# Piirikaavio-HSM213-001-SPC.net
KiCad netlist of a schematic drawn in Altium Designer
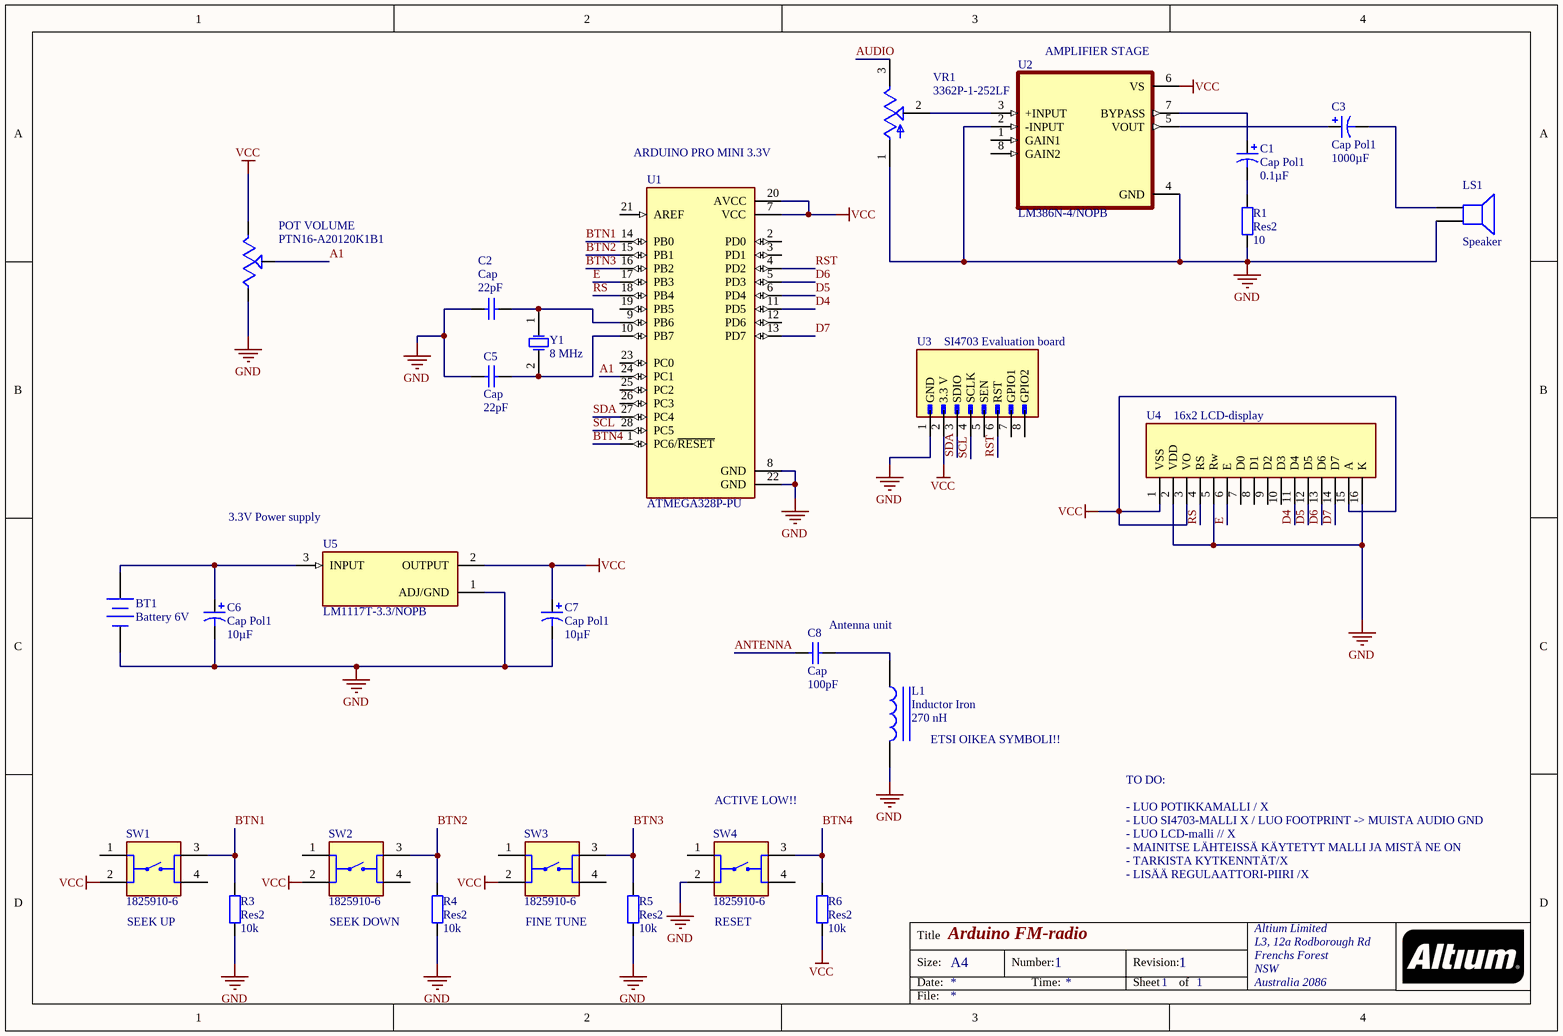
[diagram p0: Piirikaavio-HSM213-001-SPC.SchDoc]

(export (version "E")
  (design (tool "Eeschema 10.0.6"))
  (components
    (comp (ref "BT1")
      (value "Battery 6V")
      (footprint "BAT-2")
      (description "Multicell Battery")
      (fields (field (name "PUBLISHER") "Altium Limited"))
      (libsource (lib "Miscellaneous Devices") (part "Battery"))
    )
    (comp (ref "C1")
      (value "Cap Pol1")
      (footprint "RB7.6-15")
      (description "Polarized Capacitor (Radial)")
      (fields (field (name "ALTIUM_VALUE") "0.1µF") (field (name "PUBLISHER") "Altium Limited"))
      (libsource (lib "Miscellaneous Devices") (part "Cap Pol1"))
    )
    (comp (ref "C2")
      (value "Cap")
      (footprint "RAD-0.3")
      (description "Capacitor")
      (fields (field (name "ALTIUM_VALUE") "22pF") (field (name "PUBLISHER") "Altium Limited"))
      (libsource (lib "Miscellaneous Devices") (part "Cap"))
    )
    (comp (ref "C3")
      (value "Cap Pol1")
      (footprint "RB7.6-15")
      (description "Polarized Capacitor (Radial)")
      (fields (field (name "ALTIUM_VALUE") "1000µF") (field (name "PUBLISHER") "Altium Limited"))
      (libsource (lib "Miscellaneous Devices") (part "Cap Pol1"))
    )
    (comp (ref "C5")
      (value "Cap")
      (footprint "RAD-0.3")
      (description "Capacitor")
      (fields (field (name "ALTIUM_VALUE") "22pF") (field (name "PUBLISHER") "Altium Limited"))
      (libsource (lib "Miscellaneous Devices") (part "Cap"))
    )
    (comp (ref "C6")
      (value "Cap Pol1")
      (footprint "RB7.6-15")
      (description "Polarized Capacitor (Radial)")
      (fields (field (name "ALTIUM_VALUE") "10µF") (field (name "PUBLISHER") "Altium Limited"))
      (libsource (lib "Miscellaneous Devices") (part "Cap Pol1"))
    )
    (comp (ref "C7")
      (value "Cap Pol1")
      (footprint "RB7.6-15")
      (description "Polarized Capacitor (Radial)")
      (fields (field (name "ALTIUM_VALUE") "10µF") (field (name "PUBLISHER") "Altium Limited"))
      (libsource (lib "Miscellaneous Devices") (part "Cap Pol1"))
    )
    (comp (ref "C8")
      (value "Cap")
      (footprint "RAD-0.3")
      (description "Capacitor")
      (fields (field (name "ALTIUM_VALUE") "100pF") (field (name "PUBLISHER") "Altium Limited"))
      (libsource (lib "Miscellaneous Devices") (part "Cap"))
    )
    (comp (ref "L1")
      (value "Inductor Iron")
      (footprint "AXIAL-0.9")
      (description "Magnetic-Core Inductor")
      (fields (field (name "ALTIUM_VALUE") "270 nH") (field (name "PUBLISHER") "Altium Limited"))
      (libsource (lib "Miscellaneous Devices") (part "Inductor Iron"))
    )
    (comp (ref "LS1")
      (value "Speaker")
      (footprint "PIN2")
      (description "Loudspeaker")
      (fields (field (name "PUBLISHER") "Altium Limited"))
      (libsource (lib "Miscellaneous Devices") (part "Speaker"))
    )
    (comp (ref "POT VOLUME")
      (value "PTN16-A20120K1B1")
      (footprint "POT_PTN16-A20120K1B1")
      (fields (field (name "MF") "CUI Devices"))
      (libsource (lib "PTN16-A20120K1B1") (part "PTN16-A20120K1B1"))
    )
    (comp (ref "R1")
      (value "Res2")
      (footprint "AXIAL-0.4")
      (description "Resistor")
      (fields (field (name "ALTIUM_VALUE") "10") (field (name "PUBLISHER") "Altium Limited"))
      (libsource (lib "") (part "Res2_1"))
    )
    (comp (ref "R3")
      (value "Res2")
      (footprint "AXIAL-0.4")
      (description "Resistor")
      (fields (field (name "ALTIUM_VALUE") "10k") (field (name "PUBLISHER") "Altium Limited"))
      (libsource (lib "Miscellaneous Devices") (part "Res2"))
    )
    (comp (ref "R4")
      (value "Res2")
      (footprint "AXIAL-0.4")
      (description "Resistor")
      (fields (field (name "ALTIUM_VALUE") "10k") (field (name "PUBLISHER") "Altium Limited"))
      (libsource (lib "Miscellaneous Devices") (part "Res2"))
    )
    (comp (ref "R5")
      (value "Res2")
      (footprint "AXIAL-0.4")
      (description "Resistor")
      (fields (field (name "ALTIUM_VALUE") "10k") (field (name "PUBLISHER") "Altium Limited"))
      (libsource (lib "Miscellaneous Devices") (part "Res2"))
    )
    (comp (ref "R6")
      (value "Res2")
      (footprint "AXIAL-0.4")
      (description "Resistor")
      (fields (field (name "ALTIUM_VALUE") "10k") (field (name "PUBLISHER") "Altium Limited"))
      (libsource (lib "Miscellaneous Devices") (part "Res2"))
    )
    (comp (ref "SW1")
      (value "1825910-6")
      (footprint "SW_1825910-6-4")
      (description "Switch Push Button OFF (ON) SPST Round Button 0.05A 24VDC Momentary Contact PC Pins Thru-Hole")
      (fields (field (name "MF") "TE Connectivity") (field (name "DIGI-KEY_PART_NUMBER") "450-1650-ND"))
      (libsource (lib "1825910-6") (part "1825910-6"))
    )
    (comp (ref "SW2")
      (value "1825910-6")
      (footprint "SW_1825910-6-4")
      (description "Switch Push Button OFF (ON) SPST Round Button 0.05A 24VDC Momentary Contact PC Pins Thru-Hole")
      (fields (field (name "MF") "TE Connectivity") (field (name "DIGI-KEY_PART_NUMBER") "450-1650-ND"))
      (libsource (lib "1825910-6") (part "1825910-6"))
    )
    (comp (ref "SW3")
      (value "1825910-6")
      (footprint "SW_1825910-6-4")
      (description "Switch Push Button OFF (ON) SPST Round Button 0.05A 24VDC Momentary Contact PC Pins Thru-Hole")
      (fields (field (name "MF") "TE Connectivity") (field (name "DIGI-KEY_PART_NUMBER") "450-1650-ND"))
      (libsource (lib "1825910-6") (part "1825910-6"))
    )
    (comp (ref "SW4")
      (value "1825910-6")
      (footprint "SW_1825910-6-4")
      (description "Switch Push Button OFF (ON) SPST Round Button 0.05A 24VDC Momentary Contact PC Pins Thru-Hole")
      (fields (field (name "MF") "TE Connectivity") (field (name "DIGI-KEY_PART_NUMBER") "450-1650-ND"))
      (libsource (lib "1825910-6") (part "1825910-6"))
    )
    (comp (ref "U1")
      (value "ATMEGA328P-PU")
      (footprint "DIP794W46P254L2967H457Q28B")
      (description "ATmega Series 20 MHz 32 KB Flash 2 KB SRAM 8-Bit Microcontroller - DIP-28")
      (libsource (lib "ATMEGA328P-PU") (part "ATMEGA328P-PU"))
    )
    (comp (ref "U2")
      (value "LM386N-4/NOPB")
      (footprint "DIP794W45P254L959H508Q8")
      (libsource (lib "LM386N-4_NOPB") (part "LM386N-4/NOPB"))
    )
    (comp (ref "U3")
      (value "SI4703 Evaluation board")
      (footprint "HARWIN_M20-9730846")
      (fields (field (name "MF") "Harwin") (field (name "MP") "M20-9730846"))
      (libsource (lib "M20-9730846") (part "M20-9730846"))
    )
    (comp (ref "U4")
      (value "16x2 LCD-display")
      (footprint "TE_6-146276-6")
      (description "16 MODII HDR SRST B/A .100CL")
      (fields (field (name "MF") "TE Connectivity") (field (name "MP") "6-146276-6"))
      (libsource (lib "6-146276-6") (part "6-146276-6"))
    )
    (comp (ref "U5")
      (value "LM1117T-3.3/NOPB")
      (footprint "TO254P1054X470X1955-3")
      (description "800-mA 15-V linear voltage regulator")
      (fields (field (name "MF") "Texas Instruments"))
      (libsource (lib "LM1117T-3.3_NOPB") (part "LM1117T-3.3/NOPB"))
    )
    (comp (ref "VR1")
      (value "3362P-1-252LF")
      (footprint "TRIM_3362P-1-252LF")
      (description "10 kOhms Pins Through Hole Trimmer Potentiometer Cermet 1 Turn Top Adjustment")
      (fields (field (name "MF") "Bourns"))
      (libsource (lib "3362P-1-252LF") (part "3362P-1-252LF"))
    )
    (comp (ref "Y1")
      (value "8 MHz")
      (footprint "R38")
      (description "Crystal Oscillator")
      (fields (field (name "PUBLISHER") "Altium Limited"))
      (libsource (lib "Miscellaneous Devices") (part "XTAL"))
    )
  )
  (nets
    (net (code "1") (name "/A1") (class "Default")
      (node (ref "POT VOLUME") (pin "2") (pinfunction "2_2") (pintype "passive"))
      (node (ref "U1") (pin "24") (pinfunction "PC1_24") (pintype "bidirectional"))
    )
    (net (code "2") (name "/ANTENNA") (class "Default")
      (node (ref "C8") (pin "1") (pinfunction "1_1") (pintype "passive"))
    )
    (net (code "3") (name "/AUDIO") (class "Default")
      (node (ref "VR1") (pin "3") (pinfunction "CW_3") (pintype "passive"))
    )
    (net (code "4") (name "/BTN1") (class "Default")
      (node (ref "R3") (pin "1") (pinfunction "1_1") (pintype "passive"))
      (node (ref "SW1") (pin "3") (pinfunction "3_3") (pintype "passive"))
      (node (ref "U1") (pin "14") (pinfunction "PB0_14") (pintype "bidirectional"))
    )
    (net (code "5") (name "/BTN2") (class "Default")
      (node (ref "R4") (pin "1") (pinfunction "1_1") (pintype "passive"))
      (node (ref "SW2") (pin "3") (pinfunction "3_3") (pintype "passive"))
      (node (ref "U1") (pin "15") (pinfunction "PB1_15") (pintype "bidirectional"))
    )
    (net (code "6") (name "/BTN3") (class "Default")
      (node (ref "R5") (pin "1") (pinfunction "1_1") (pintype "passive"))
      (node (ref "SW3") (pin "3") (pinfunction "3_3") (pintype "passive"))
      (node (ref "U1") (pin "16") (pinfunction "PB2_16") (pintype "bidirectional"))
    )
    (net (code "7") (name "/BTN4") (class "Default")
      (node (ref "R6") (pin "1") (pinfunction "1_1") (pintype "passive"))
      (node (ref "SW4") (pin "3") (pinfunction "3_3") (pintype "passive"))
      (node (ref "U1") (pin "1") (pinfunction "PC6/~{RESET}_1") (pintype "bidirectional"))
    )
    (net (code "8") (name "/D4") (class "Default")
      (node (ref "U1") (pin "11") (pinfunction "PD5_11") (pintype "bidirectional"))
      (node (ref "U4") (pin "11") (pinfunction "D4_11") (pintype "passive"))
    )
    (net (code "9") (name "/D5") (class "Default")
      (node (ref "U1") (pin "6") (pinfunction "PD4_6") (pintype "bidirectional"))
      (node (ref "U4") (pin "12") (pinfunction "D5_12") (pintype "passive"))
    )
    (net (code "10") (name "/D6") (class "Default")
      (node (ref "U1") (pin "5") (pinfunction "PD3_5") (pintype "bidirectional"))
      (node (ref "U4") (pin "13") (pinfunction "D6_13") (pintype "passive"))
    )
    (net (code "11") (name "/D7") (class "Default")
      (node (ref "U1") (pin "13") (pinfunction "PD7_13") (pintype "bidirectional"))
      (node (ref "U4") (pin "14") (pinfunction "D7_14") (pintype "passive"))
    )
    (net (code "12") (name "/E") (class "Default")
      (node (ref "U1") (pin "17") (pinfunction "PB3_17") (pintype "bidirectional"))
      (node (ref "U4") (pin "6") (pinfunction "E_6") (pintype "passive"))
    )
    (net (code "13") (name "/RS") (class "Default")
      (node (ref "U1") (pin "18") (pinfunction "PB4_18") (pintype "bidirectional"))
      (node (ref "U4") (pin "4") (pinfunction "RS_4") (pintype "passive"))
    )
    (net (code "14") (name "/RST") (class "Default")
      (node (ref "U1") (pin "4") (pinfunction "PD2_4") (pintype "bidirectional"))
      (node (ref "U3") (pin "6") (pinfunction "RST_6") (pintype "passive"))
    )
    (net (code "15") (name "/SCL") (class "Default")
      (node (ref "U1") (pin "28") (pinfunction "PC5_28") (pintype "bidirectional"))
      (node (ref "U3") (pin "4") (pinfunction "SCLK_4") (pintype "passive"))
    )
    (net (code "16") (name "/SDA") (class "Default")
      (node (ref "U1") (pin "27") (pinfunction "PC4_27") (pintype "bidirectional"))
      (node (ref "U3") (pin "3") (pinfunction "SDIO_3") (pintype "passive"))
    )
    (net (code "17") (name "GND") (class "Default")
      (node (ref "BT1") (pin "2") (pinfunction "-_2") (pintype "passive"))
      (node (ref "C2") (pin "1") (pinfunction "1_1") (pintype "passive"))
      (node (ref "C5") (pin "1") (pinfunction "1_1") (pintype "passive"))
      (node (ref "C6") (pin "2") (pinfunction "2_2") (pintype "passive"))
      (node (ref "C7") (pin "2") (pinfunction "2_2") (pintype "passive"))
      (node (ref "L1") (pin "2") (pinfunction "2_2") (pintype "passive"))
      (node (ref "LS1") (pin "2") (pinfunction "2_2") (pintype "passive"))
      (node (ref "POT VOLUME") (pin "1") (pinfunction "1_1") (pintype "passive"))
      (node (ref "R1") (pin "1") (pinfunction "1_1") (pintype "passive"))
      (node (ref "R3") (pin "2") (pinfunction "2_2") (pintype "passive"))
      (node (ref "R4") (pin "2") (pinfunction "2_2") (pintype "passive"))
      (node (ref "R5") (pin "2") (pinfunction "2_2") (pintype "passive"))
      (node (ref "SW4") (pin "2") (pinfunction "2_2") (pintype "passive"))
      (node (ref "U1") (pin "22") (pinfunction "GND_22") (pintype "power_in"))
      (node (ref "U1") (pin "8") (pinfunction "GND_8") (pintype "power_in"))
      (node (ref "U2") (pin "2") (pinfunction "-INPUT_2") (pintype "input"))
      (node (ref "U2") (pin "4") (pinfunction "GND_4") (pintype "power_in"))
      (node (ref "U3") (pin "1") (pinfunction "GND_1") (pintype "passive"))
      (node (ref "U4") (pin "16") (pinfunction "K_16") (pintype "passive"))
      (node (ref "U4") (pin "2") (pinfunction "VDD_2") (pintype "passive"))
      (node (ref "U4") (pin "5") (pinfunction "Rw_5") (pintype "passive"))
      (node (ref "U5") (pin "1") (pinfunction "ADJ/GND_1") (pintype "power_in"))
      (node (ref "VR1") (pin "1") (pinfunction "CCW_1") (pintype "passive"))
    )
    (net (code "18") (name "Net-(BT1-+)") (class "Default")
      (node (ref "BT1") (pin "1") (pinfunction "+_1") (pintype "passive"))
      (node (ref "C6") (pin "1") (pinfunction "1_1") (pintype "passive"))
      (node (ref "U5") (pin "3") (pinfunction "INPUT_3") (pintype "input"))
    )
    (net (code "19") (name "Net-(C1-Pad2)") (class "Default")
      (node (ref "C1") (pin "2") (pinfunction "2_2") (pintype "passive"))
      (node (ref "R1") (pin "2") (pinfunction "2_2") (pintype "passive"))
    )
    (net (code "20") (name "Net-(C3-Pad2)") (class "Default")
      (node (ref "C3") (pin "2") (pinfunction "2_2") (pintype "passive"))
      (node (ref "LS1") (pin "1") (pinfunction "1_1") (pintype "passive"))
    )
    (net (code "21") (name "Net-(C8-Pad2)") (class "Default")
      (node (ref "C8") (pin "2") (pinfunction "2_2") (pintype "passive"))
      (node (ref "L1") (pin "1") (pinfunction "1_1") (pintype "passive"))
    )
    (net (code "22") (name "Net-(U1-PB6)") (class "Default")
      (node (ref "C2") (pin "2") (pinfunction "2_2") (pintype "passive"))
      (node (ref "U1") (pin "9") (pinfunction "PB6_9") (pintype "bidirectional"))
      (node (ref "Y1") (pin "1") (pinfunction "OSC1_1") (pintype "passive"))
    )
    (net (code "23") (name "Net-(U1-PB7)") (class "Default")
      (node (ref "C5") (pin "2") (pinfunction "2_2") (pintype "passive"))
      (node (ref "U1") (pin "10") (pinfunction "PB7_10") (pintype "bidirectional"))
      (node (ref "Y1") (pin "2") (pinfunction "OSC2_2") (pintype "passive"))
    )
    (net (code "24") (name "Net-(U2-+INPUT)") (class "Default")
      (node (ref "U2") (pin "3") (pinfunction "+INPUT_3") (pintype "input"))
      (node (ref "VR1") (pin "2") (pinfunction "WIPER_2") (pintype "passive"))
    )
    (net (code "25") (name "Net-(U2-BYPASS)") (class "Default")
      (node (ref "C1") (pin "1") (pinfunction "1_1") (pintype "passive"))
      (node (ref "U2") (pin "7") (pinfunction "BYPASS_7") (pintype "output"))
    )
    (net (code "26") (name "Net-(U2-VOUT)") (class "Default")
      (node (ref "C3") (pin "1") (pinfunction "1_1") (pintype "passive"))
      (node (ref "U2") (pin "5") (pinfunction "VOUT_5") (pintype "output"))
    )
    (net (code "27") (name "VCC") (class "Default")
      (node (ref "C7") (pin "1") (pinfunction "1_1") (pintype "passive"))
      (node (ref "POT VOLUME") (pin "3") (pinfunction "3_3") (pintype "passive"))
      (node (ref "R6") (pin "2") (pinfunction "2_2") (pintype "passive"))
      (node (ref "SW1") (pin "2") (pinfunction "2_2") (pintype "passive"))
      (node (ref "SW2") (pin "2") (pinfunction "2_2") (pintype "passive"))
      (node (ref "SW3") (pin "2") (pinfunction "2_2") (pintype "passive"))
      (node (ref "U1") (pin "20") (pinfunction "AVCC_20") (pintype "power_in"))
      (node (ref "U1") (pin "7") (pinfunction "VCC_7") (pintype "power_in"))
      (node (ref "U2") (pin "6") (pinfunction "VS_6") (pintype "power_in"))
      (node (ref "U3") (pin "2") (pinfunction "3.3_V_2") (pintype "passive"))
      (node (ref "U4") (pin "1") (pinfunction "VSS_1") (pintype "passive"))
      (node (ref "U4") (pin "15") (pinfunction "A_15") (pintype "passive"))
      (node (ref "U4") (pin "3") (pinfunction "VO_3") (pintype "passive"))
      (node (ref "U5") (pin "2") (pinfunction "OUTPUT_2") (pintype "power_in"))
    )
    (net (code "28") (name "unconnected-(SW1-Pad1)") (class "Default")
      (node (ref "SW1") (pin "1") (pinfunction "1_1") (pintype "passive"))
    )
    (net (code "29") (name "unconnected-(SW1-Pad4)") (class "Default")
      (node (ref "SW1") (pin "4") (pinfunction "4_4") (pintype "passive"))
    )
    (net (code "30") (name "unconnected-(SW2-Pad1)") (class "Default")
      (node (ref "SW2") (pin "1") (pinfunction "1_1") (pintype "passive"))
    )
    (net (code "31") (name "unconnected-(SW2-Pad4)") (class "Default")
      (node (ref "SW2") (pin "4") (pinfunction "4_4") (pintype "passive"))
    )
    (net (code "32") (name "unconnected-(SW3-Pad1)") (class "Default")
      (node (ref "SW3") (pin "1") (pinfunction "1_1") (pintype "passive"))
    )
    (net (code "33") (name "unconnected-(SW3-Pad4)") (class "Default")
      (node (ref "SW3") (pin "4") (pinfunction "4_4") (pintype "passive"))
    )
    (net (code "34") (name "unconnected-(SW4-Pad1)") (class "Default")
      (node (ref "SW4") (pin "1") (pinfunction "1_1") (pintype "passive"))
    )
    (net (code "35") (name "unconnected-(SW4-Pad4)") (class "Default")
      (node (ref "SW4") (pin "4") (pinfunction "4_4") (pintype "passive"))
    )
    (net (code "36") (name "unconnected-(U1-AREF-Pad21)") (class "Default")
      (node (ref "U1") (pin "21") (pinfunction "AREF_21") (pintype "input"))
    )
    (net (code "37") (name "unconnected-(U1-PB5-Pad19)") (class "Default")
      (node (ref "U1") (pin "19") (pinfunction "PB5_19") (pintype "bidirectional"))
    )
    (net (code "38") (name "unconnected-(U1-PC0-Pad23)") (class "Default")
      (node (ref "U1") (pin "23") (pinfunction "PC0_23") (pintype "bidirectional"))
    )
    (net (code "39") (name "unconnected-(U1-PC2-Pad25)") (class "Default")
      (node (ref "U1") (pin "25") (pinfunction "PC2_25") (pintype "bidirectional"))
    )
    (net (code "40") (name "unconnected-(U1-PC3-Pad26)") (class "Default")
      (node (ref "U1") (pin "26") (pinfunction "PC3_26") (pintype "bidirectional"))
    )
    (net (code "41") (name "unconnected-(U1-PD0-Pad2)") (class "Default")
      (node (ref "U1") (pin "2") (pinfunction "PD0_2") (pintype "bidirectional"))
    )
    (net (code "42") (name "unconnected-(U1-PD1-Pad3)") (class "Default")
      (node (ref "U1") (pin "3") (pinfunction "PD1_3") (pintype "bidirectional"))
    )
    (net (code "43") (name "unconnected-(U1-PD6-Pad12)") (class "Default")
      (node (ref "U1") (pin "12") (pinfunction "PD6_12") (pintype "bidirectional"))
    )
    (net (code "44") (name "unconnected-(U2-GAIN1-Pad1)") (class "Default")
      (node (ref "U2") (pin "1") (pinfunction "GAIN1_1") (pintype "input"))
    )
    (net (code "45") (name "unconnected-(U2-GAIN2-Pad8)") (class "Default")
      (node (ref "U2") (pin "8") (pinfunction "GAIN2_8") (pintype "input"))
    )
    (net (code "46") (name "unconnected-(U3-GPIO1-Pad7)") (class "Default")
      (node (ref "U3") (pin "7") (pinfunction "GPIO1_7") (pintype "passive"))
    )
    (net (code "47") (name "unconnected-(U3-GPIO2-Pad8)") (class "Default")
      (node (ref "U3") (pin "8") (pinfunction "GPIO2_8") (pintype "passive"))
    )
    (net (code "48") (name "unconnected-(U3-SEN-Pad5)") (class "Default")
      (node (ref "U3") (pin "5") (pinfunction "SEN_5") (pintype "passive"))
    )
    (net (code "49") (name "unconnected-(U4-D0-Pad7)") (class "Default")
      (node (ref "U4") (pin "7") (pinfunction "D0_7") (pintype "passive"))
    )
    (net (code "50") (name "unconnected-(U4-D1-Pad8)") (class "Default")
      (node (ref "U4") (pin "8") (pinfunction "D1_8") (pintype "passive"))
    )
    (net (code "51") (name "unconnected-(U4-D2-Pad9)") (class "Default")
      (node (ref "U4") (pin "9") (pinfunction "D2_9") (pintype "passive"))
    )
    (net (code "52") (name "unconnected-(U4-D3-Pad10)") (class "Default")
      (node (ref "U4") (pin "10") (pinfunction "D3_10") (pintype "passive"))
    )
  )
)
